# Memory_SRAM.net
KiCad netlist of a schematic drawn in Altium Designer
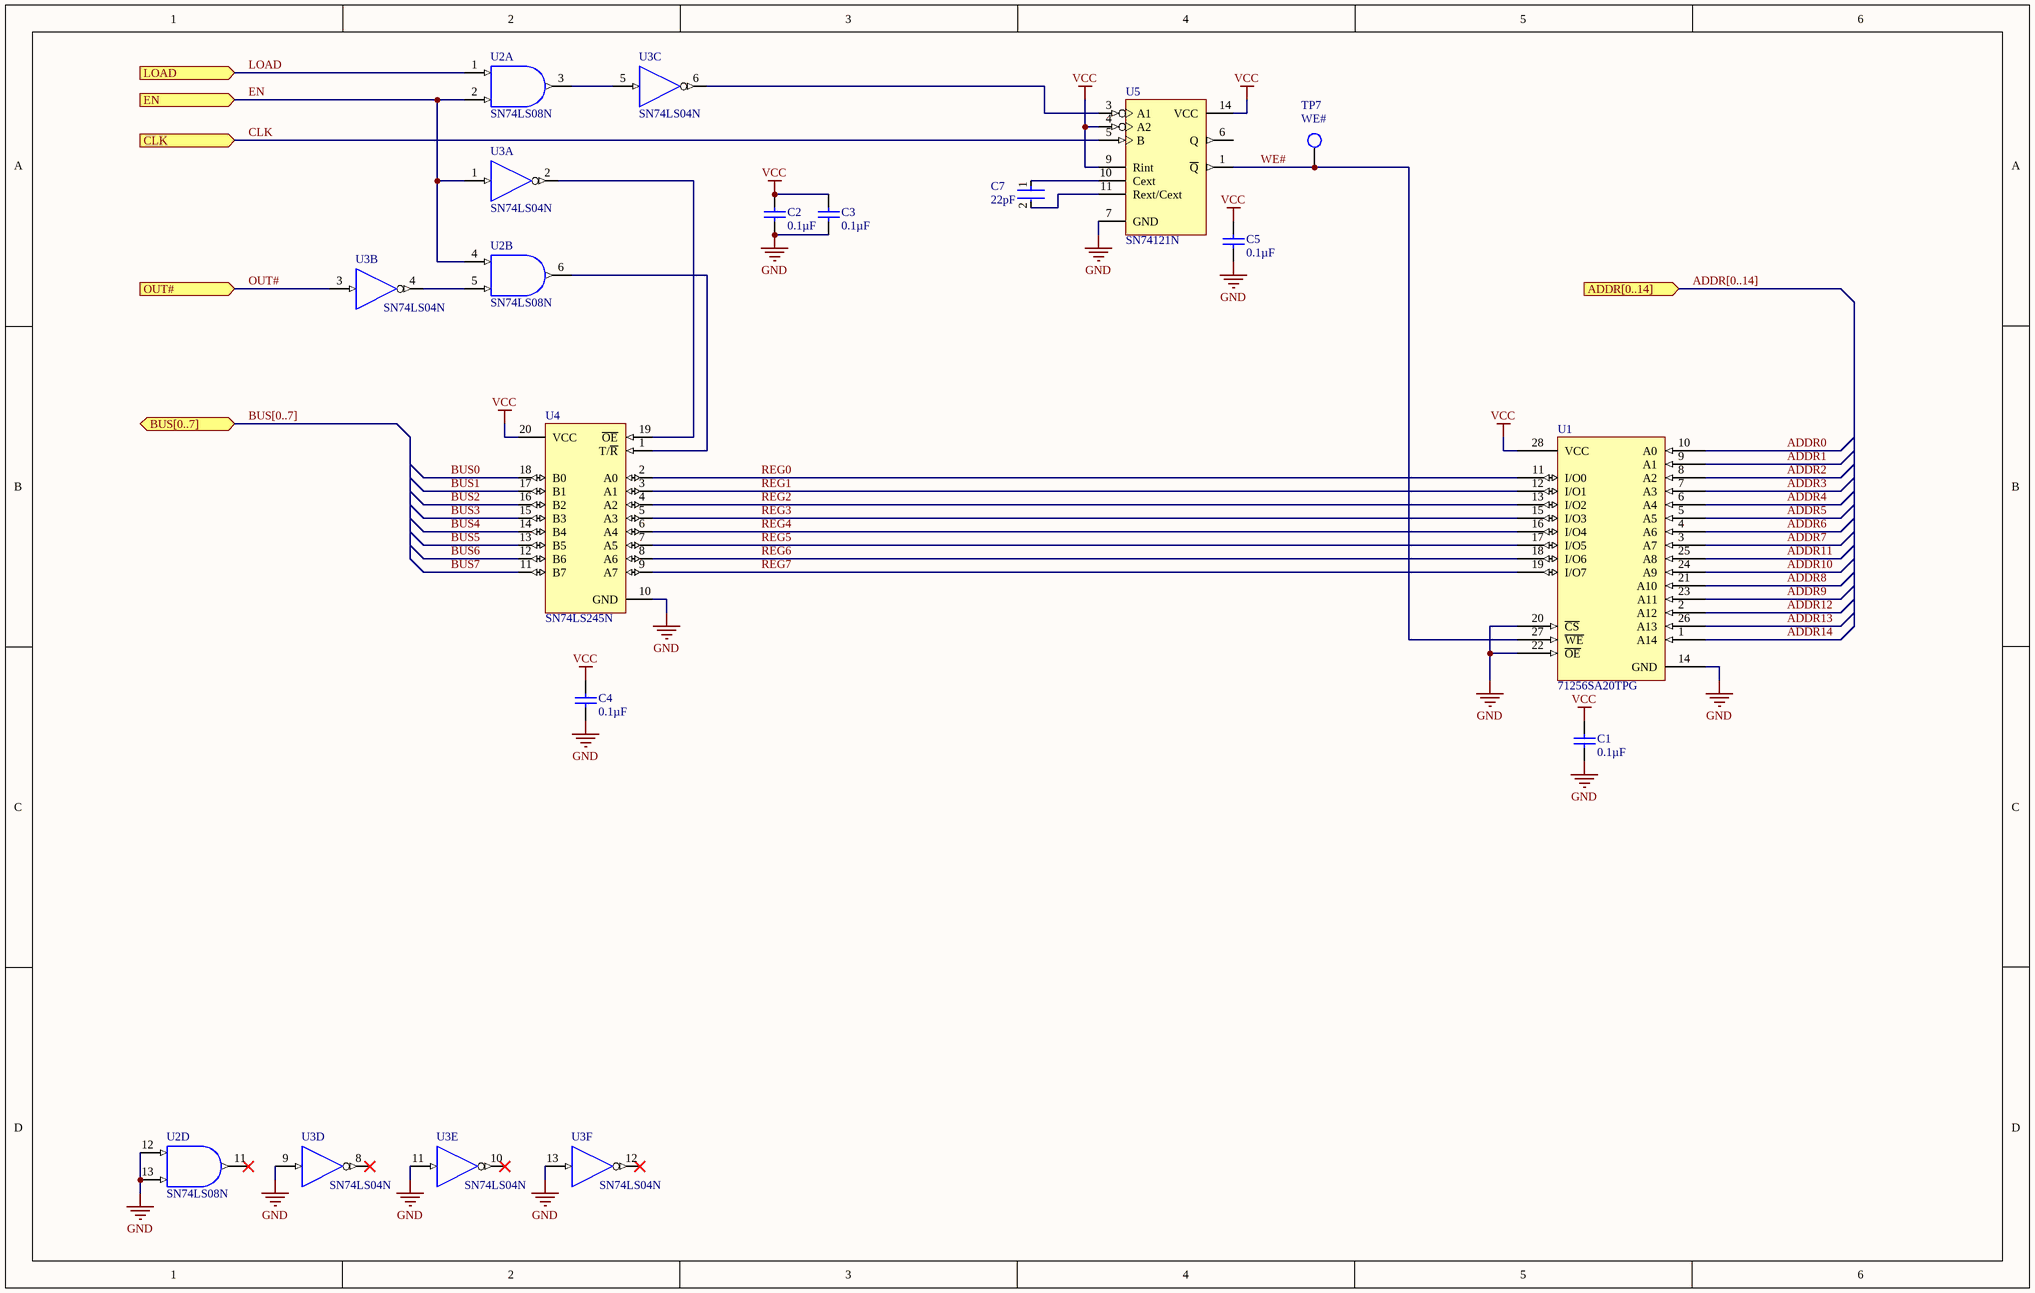
[diagram p0: Memory_SRAM.SchDoc]

(export (version "E")
  (design (tool "Eeschema 10.0.6"))
  (components
    (comp (ref "C1")
      (value "K104K15X7RF5TL2")
      (footprint "VISH-K104K15X7RF5TL2")
      (description "Ceramic Capacitor, 100 nF, +/- 10%, 50 V, -55 to 125 degC, 2-Pin THD, RoHS, Tape and Reel")
      (fields
        (field (name "MANUFACTURER") "Vishay")
        (field (name "TOLERANCE") "±10%")
        (field (name "CAPACITANCE") "0.1µF")
      )
      (libsource (lib "Altium Content Vault") (part "CAP-NP-2"))
    )
    (comp (ref "C2")
      (value "K104K15X7RF5TL2")
      (footprint "VISH-K104K15X7RF5TL2")
      (description "Ceramic Capacitor, 100 nF, +/- 10%, 50 V, -55 to 125 degC, 2-Pin THD, RoHS, Tape and Reel")
      (fields
        (field (name "MANUFACTURER") "Vishay")
        (field (name "TOLERANCE") "±10%")
        (field (name "CAPACITANCE") "0.1µF")
      )
      (libsource (lib "Altium Content Vault") (part "CAP-NP-2"))
    )
    (comp (ref "C3")
      (value "K104K15X7RF5TL2")
      (footprint "VISH-K104K15X7RF5TL2")
      (description "Ceramic Capacitor, 100 nF, +/- 10%, 50 V, -55 to 125 degC, 2-Pin THD, RoHS, Tape and Reel")
      (fields
        (field (name "MANUFACTURER") "Vishay")
        (field (name "TOLERANCE") "±10%")
        (field (name "CAPACITANCE") "0.1µF")
      )
      (libsource (lib "Altium Content Vault") (part "CAP-NP-2"))
    )
    (comp (ref "C4")
      (value "K104K15X7RF5TL2")
      (footprint "VISH-K104K15X7RF5TL2")
      (description "Ceramic Capacitor, 100 nF, +/- 10%, 50 V, -55 to 125 degC, 2-Pin THD, RoHS, Tape and Reel")
      (fields
        (field (name "MANUFACTURER") "Vishay")
        (field (name "TOLERANCE") "±10%")
        (field (name "CAPACITANCE") "0.1µF")
      )
      (libsource (lib "Altium Content Vault") (part "CAP-NP-2"))
    )
    (comp (ref "C5")
      (value "K104K15X7RF5TL2")
      (footprint "VISH-K104K15X7RF5TL2")
      (description "Ceramic Capacitor, 100 nF, +/- 10%, 50 V, -55 to 125 degC, 2-Pin THD, RoHS, Tape and Reel")
      (fields
        (field (name "MANUFACTURER") "Vishay")
        (field (name "TOLERANCE") "±10%")
        (field (name "CAPACITANCE") "0.1µF")
      )
      (libsource (lib "Altium Content Vault") (part "CAP-NP-2"))
    )
    (comp (ref "C7")
      (value "RDE5C1H220J0M1H03A")
      (footprint "FP-RDE0M1-MFG")
      (description "Ceramic Capacitor 22pF ±5% 50V C0G Radial")
      (fields (field (name "CAPACITANCE") "22pF") (field (name "TOLERANCE") "5%"))
      (libsource (lib "Altium Content Vault") (part "b4654b650e69147ec39a6b967a45e02"))
    )
    (comp (ref "TP7") (value "WE#") (footprint "KSTN-5011_V") (libsource (lib "TP") (part "TP")))
    (comp (ref "U1")
      (value "71256SA20TPG")
      (footprint "JT028")
      (libsource (lib "Schlib1") (part "71256SA20TPG"))
    )
    (comp (ref "U2")
      (value "SN74LS08N")
      (footprint "N014")
      (description "Quadruple 2-Input Positive-AND Gate")
      (fields (field (name "PUBLISHER") "Altium Limited"))
      (libsource (lib "TI Logic Gate 2") (part "SN74LS08N"))
    )
    (comp (ref "U3")
      (value "SN74LS04N")
      (footprint "N014")
      (description "Hex Inverter")
      (fields (field (name "PUBLISHER") "Altium Limited"))
      (libsource (lib "TI Logic Gate 2") (part "SN74LS04N"))
    )
    (comp (ref "U4")
      (value "SN74LS245N")
      (footprint "N020")
      (description "Octal Bus Transceiver with 3-State Outputs")
      (fields (field (name "PUBLISHER") "Altium Limited"))
      (libsource (lib "TI Interface 8-Bit Line Transceiver") (part "SN74LS245N"))
    )
    (comp (ref "U5")
      (value "SN74121N")
      (footprint "N014")
      (description "Monostable Multivibrator with Schmitt-Trigger Inputs")
      (fields (field (name "PUBLISHER") "Altium Limited"))
      (libsource (lib "TI Logic Multivibrator") (part "SN74121N"))
    )
  )
  (nets
    (net (code "1") (name "/ADDR0") (class "Default")
      (node (ref "U1") (pin "10") (pinfunction "A0_10") (pintype "input"))
    )
    (net (code "2") (name "/ADDR1") (class "Default")
      (node (ref "U1") (pin "9") (pinfunction "A1_9") (pintype "input"))
    )
    (net (code "3") (name "/ADDR2") (class "Default")
      (node (ref "U1") (pin "8") (pinfunction "A2_8") (pintype "input"))
    )
    (net (code "4") (name "/ADDR3") (class "Default")
      (node (ref "U1") (pin "7") (pinfunction "A3_7") (pintype "input"))
    )
    (net (code "5") (name "/ADDR4") (class "Default")
      (node (ref "U1") (pin "6") (pinfunction "A4_6") (pintype "input"))
    )
    (net (code "6") (name "/ADDR5") (class "Default")
      (node (ref "U1") (pin "5") (pinfunction "A5_5") (pintype "input"))
    )
    (net (code "7") (name "/ADDR6") (class "Default")
      (node (ref "U1") (pin "4") (pinfunction "A6_4") (pintype "input"))
    )
    (net (code "8") (name "/ADDR7") (class "Default")
      (node (ref "U1") (pin "3") (pinfunction "A7_3") (pintype "input"))
    )
    (net (code "9") (name "/ADDR8") (class "Default")
      (node (ref "U1") (pin "21") (pinfunction "A10_21") (pintype "input"))
    )
    (net (code "10") (name "/ADDR9") (class "Default")
      (node (ref "U1") (pin "23") (pinfunction "A11_23") (pintype "input"))
    )
    (net (code "11") (name "/ADDR10") (class "Default")
      (node (ref "U1") (pin "24") (pinfunction "A9_24") (pintype "input"))
    )
    (net (code "12") (name "/ADDR11") (class "Default")
      (node (ref "U1") (pin "25") (pinfunction "A8_25") (pintype "input"))
    )
    (net (code "13") (name "/ADDR12") (class "Default")
      (node (ref "U1") (pin "2") (pinfunction "A12_2") (pintype "input"))
    )
    (net (code "14") (name "/ADDR13") (class "Default")
      (node (ref "U1") (pin "26") (pinfunction "A13_26") (pintype "input"))
    )
    (net (code "15") (name "/ADDR14") (class "Default")
      (node (ref "U1") (pin "1") (pinfunction "A14_1") (pintype "input"))
    )
    (net (code "17") (name "/BUS0") (class "Default")
      (node (ref "U4") (pin "18") (pinfunction "B0_18") (pintype "bidirectional"))
    )
    (net (code "18") (name "/BUS1") (class "Default")
      (node (ref "U4") (pin "17") (pinfunction "B1_17") (pintype "bidirectional"))
    )
    (net (code "19") (name "/BUS2") (class "Default")
      (node (ref "U4") (pin "16") (pinfunction "B2_16") (pintype "bidirectional"))
    )
    (net (code "20") (name "/BUS3") (class "Default")
      (node (ref "U4") (pin "15") (pinfunction "B3_15") (pintype "bidirectional"))
    )
    (net (code "21") (name "/BUS4") (class "Default")
      (node (ref "U4") (pin "14") (pinfunction "B4_14") (pintype "bidirectional"))
    )
    (net (code "22") (name "/BUS5") (class "Default")
      (node (ref "U4") (pin "13") (pinfunction "B5_13") (pintype "bidirectional"))
    )
    (net (code "23") (name "/BUS6") (class "Default")
      (node (ref "U4") (pin "12") (pinfunction "B6_12") (pintype "bidirectional"))
    )
    (net (code "24") (name "/BUS7") (class "Default")
      (node (ref "U4") (pin "11") (pinfunction "B7_11") (pintype "bidirectional"))
    )
    (net (code "26") (name "/CLK") (class "Default")
      (node (ref "U5") (pin "5") (pinfunction "B_5") (pintype "input"))
    )
    (net (code "27") (name "/EN") (class "Default")
      (node (ref "U2") (pin "2") (pinfunction "B_2") (pintype "input"))
      (node (ref "U2") (pin "4") (pinfunction "A_4") (pintype "input"))
      (node (ref "U3") (pin "1") (pinfunction "A_1") (pintype "input"))
    )
    (net (code "28") (name "/LOAD") (class "Default")
      (node (ref "U2") (pin "1") (pinfunction "A_1") (pintype "input"))
    )
    (net (code "29") (name "/OUT#") (class "Default")
      (node (ref "U3") (pin "3") (pinfunction "A_3") (pintype "input"))
    )
    (net (code "30") (name "/REG0") (class "Default")
      (node (ref "U1") (pin "11") (pinfunction "I/O0_11") (pintype "bidirectional"))
      (node (ref "U4") (pin "2") (pinfunction "A0_2") (pintype "bidirectional"))
    )
    (net (code "31") (name "/REG1") (class "Default")
      (node (ref "U1") (pin "12") (pinfunction "I/O1_12") (pintype "bidirectional"))
      (node (ref "U4") (pin "3") (pinfunction "A1_3") (pintype "bidirectional"))
    )
    (net (code "32") (name "/REG2") (class "Default")
      (node (ref "U1") (pin "13") (pinfunction "I/O2_13") (pintype "bidirectional"))
      (node (ref "U4") (pin "4") (pinfunction "A2_4") (pintype "bidirectional"))
    )
    (net (code "33") (name "/REG3") (class "Default")
      (node (ref "U1") (pin "15") (pinfunction "I/O3_15") (pintype "bidirectional"))
      (node (ref "U4") (pin "5") (pinfunction "A3_5") (pintype "bidirectional"))
    )
    (net (code "34") (name "/REG4") (class "Default")
      (node (ref "U1") (pin "16") (pinfunction "I/O4_16") (pintype "bidirectional"))
      (node (ref "U4") (pin "6") (pinfunction "A4_6") (pintype "bidirectional"))
    )
    (net (code "35") (name "/REG5") (class "Default")
      (node (ref "U1") (pin "17") (pinfunction "I/O5_17") (pintype "bidirectional"))
      (node (ref "U4") (pin "7") (pinfunction "A5_7") (pintype "bidirectional"))
    )
    (net (code "36") (name "/REG6") (class "Default")
      (node (ref "U1") (pin "18") (pinfunction "I/O6_18") (pintype "bidirectional"))
      (node (ref "U4") (pin "8") (pinfunction "A6_8") (pintype "bidirectional"))
    )
    (net (code "37") (name "/REG7") (class "Default")
      (node (ref "U1") (pin "19") (pinfunction "I/O7_19") (pintype "bidirectional"))
      (node (ref "U4") (pin "9") (pinfunction "A7_9") (pintype "bidirectional"))
    )
    (net (code "38") (name "/WE#") (class "Default")
      (node (ref "TP7") (pin "1") (pintype "passive"))
      (node (ref "U1") (pin "27") (pinfunction "~{WE}_27") (pintype "input"))
      (node (ref "U5") (pin "1") (pinfunction "~{Q}_1") (pintype "output"))
    )
    (net (code "39") (name "GND") (class "Default")
      (node (ref "C1") (pin "2") (pinfunction "2_2") (pintype "passive"))
      (node (ref "C2") (pin "2") (pinfunction "2_2") (pintype "passive"))
      (node (ref "C3") (pin "2") (pinfunction "2_2") (pintype "passive"))
      (node (ref "C4") (pin "2") (pinfunction "2_2") (pintype "passive"))
      (node (ref "C5") (pin "2") (pinfunction "2_2") (pintype "passive"))
      (node (ref "U1") (pin "14") (pinfunction "GND_14") (pintype "power_in"))
      (node (ref "U1") (pin "20") (pinfunction "~{CS}_20") (pintype "input"))
      (node (ref "U1") (pin "22") (pinfunction "~{OE}_22") (pintype "input"))
      (node (ref "U2") (pin "12") (pinfunction "A_12") (pintype "input"))
      (node (ref "U2") (pin "13") (pinfunction "B_13") (pintype "input"))
      (node (ref "U2") (pin "7") (pinfunction "GND_7") (pintype "power_in"))
      (node (ref "U3") (pin "11") (pinfunction "A_11") (pintype "input"))
      (node (ref "U3") (pin "13") (pinfunction "A_13") (pintype "input"))
      (node (ref "U3") (pin "7") (pinfunction "GND_7") (pintype "power_in"))
      (node (ref "U3") (pin "9") (pinfunction "A_9") (pintype "input"))
      (node (ref "U4") (pin "10") (pinfunction "GND_10") (pintype "power_in"))
      (node (ref "U5") (pin "7") (pinfunction "GND_7") (pintype "power_in"))
    )
    (net (code "40") (name "Net-(U2A-Y)") (class "Default")
      (node (ref "U2") (pin "3") (pinfunction "Y_3") (pintype "output"))
      (node (ref "U3") (pin "5") (pinfunction "A_5") (pintype "input"))
    )
    (net (code "41") (name "Net-(U2B-B)") (class "Default")
      (node (ref "U2") (pin "5") (pinfunction "B_5") (pintype "input"))
      (node (ref "U3") (pin "4") (pinfunction "Y_4") (pintype "output"))
    )
    (net (code "42") (name "Net-(U2B-Y)") (class "Default")
      (node (ref "U2") (pin "6") (pinfunction "Y_6") (pintype "output"))
      (node (ref "U4") (pin "1") (pinfunction "T/~{R}_1") (pintype "input"))
    )
    (net (code "43") (name "Net-(U3A-Y)") (class "Default")
      (node (ref "U3") (pin "2") (pinfunction "Y_2") (pintype "output"))
      (node (ref "U4") (pin "19") (pinfunction "~{OE}_19") (pintype "input"))
    )
    (net (code "44") (name "Net-(U3C-Y)") (class "Default")
      (node (ref "U3") (pin "6") (pinfunction "Y_6") (pintype "output"))
      (node (ref "U5") (pin "3") (pinfunction "A1_3") (pintype "input"))
    )
    (net (code "45") (name "Net-(U5-Cext)") (class "Default")
      (node (ref "C7") (pin "1") (pinfunction "1_1") (pintype "passive"))
      (node (ref "U5") (pin "10") (pinfunction "Cext_10") (pintype "passive"))
    )
    (net (code "46") (name "Net-(U5-Rext{slash}Cext)") (class "Default")
      (node (ref "C7") (pin "2") (pinfunction "2_2") (pintype "passive"))
      (node (ref "U5") (pin "11") (pinfunction "Rext/Cext_11") (pintype "passive"))
    )
    (net (code "47") (name "VCC") (class "Default")
      (node (ref "C1") (pin "1") (pinfunction "1_1") (pintype "passive"))
      (node (ref "C2") (pin "1") (pinfunction "1_1") (pintype "passive"))
      (node (ref "C3") (pin "1") (pinfunction "1_1") (pintype "passive"))
      (node (ref "C4") (pin "1") (pinfunction "1_1") (pintype "passive"))
      (node (ref "C5") (pin "1") (pinfunction "1_1") (pintype "passive"))
      (node (ref "U1") (pin "28") (pinfunction "VCC_28") (pintype "power_in"))
      (node (ref "U2") (pin "14") (pinfunction "VCC_14") (pintype "power_in"))
      (node (ref "U3") (pin "14") (pinfunction "VCC_14") (pintype "power_in"))
      (node (ref "U4") (pin "20") (pinfunction "VCC_20") (pintype "power_in"))
      (node (ref "U5") (pin "14") (pinfunction "VCC_14") (pintype "power_in"))
      (node (ref "U5") (pin "4") (pinfunction "A2_4") (pintype "input"))
      (node (ref "U5") (pin "9") (pinfunction "Rint_9") (pintype "passive"))
    )
    (net (code "48") (name "unconnected-(U2D-Y-Pad11)") (class "Default")
      (node (ref "U2") (pin "11") (pinfunction "Y_11") (pintype "output+no_connect"))
    )
    (net (code "49") (name "unconnected-(U3D-Y-Pad8)") (class "Default")
      (node (ref "U3") (pin "8") (pinfunction "Y_8") (pintype "output+no_connect"))
    )
    (net (code "50") (name "unconnected-(U3E-Y-Pad10)") (class "Default")
      (node (ref "U3") (pin "10") (pinfunction "Y_10") (pintype "output+no_connect"))
    )
    (net (code "51") (name "unconnected-(U3F-Y-Pad12)") (class "Default")
      (node (ref "U3") (pin "12") (pinfunction "Y_12") (pintype "output+no_connect"))
    )
    (net (code "52") (name "unconnected-(U5-Q-Pad6)") (class "Default")
      (node (ref "U5") (pin "6") (pinfunction "Q_6") (pintype "output"))
    )
  )
)
